# FNIRS_Carrier_BT_Series.net
KiCad netlist of a schematic drawn in EAGLE
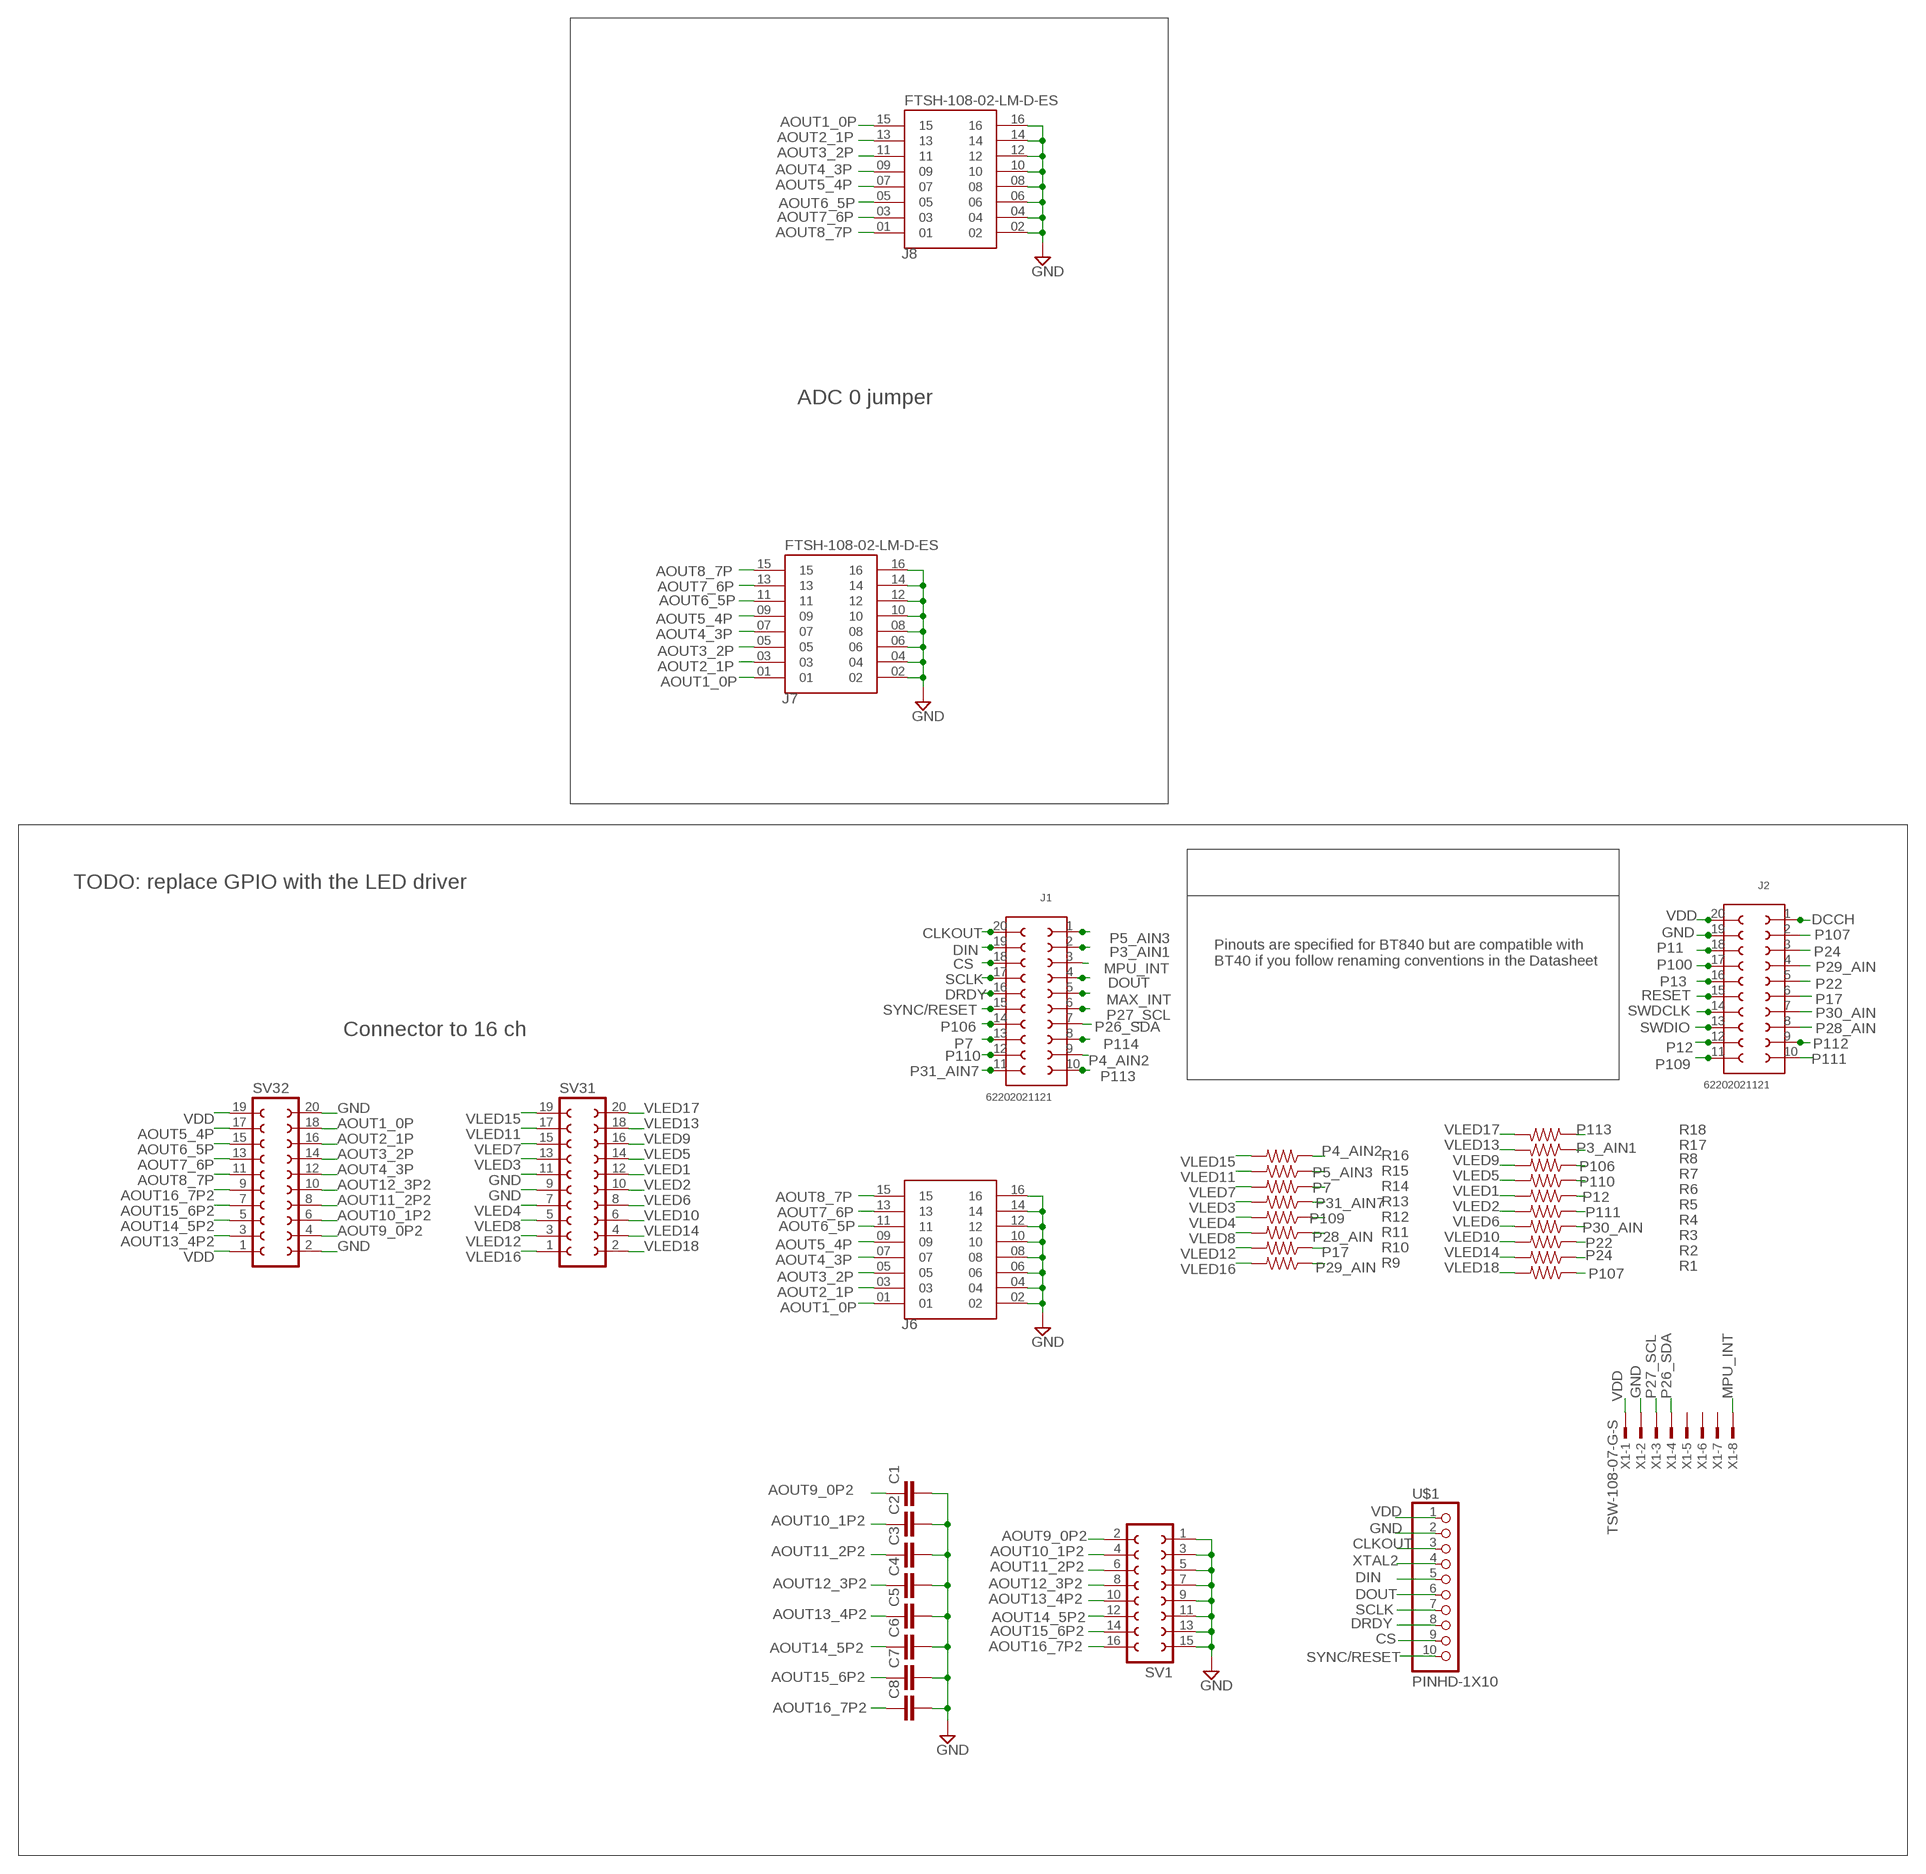
[diagram p0: schematic, sheet 1]

(export (version "E")
  (design (tool "Eeschema 10.0.6"))
  (components
    (comp (ref "C1")
      (value "C2.5/2")
      (footprint "eagle-import:C2.5-2")
      (libsource (lib "eagle-import") (part "C2.5/2"))
    )
    (comp (ref "C2")
      (value "C2.5/2")
      (footprint "eagle-import:C2.5-2")
      (libsource (lib "eagle-import") (part "C2.5/2"))
    )
    (comp (ref "C3")
      (value "C2.5/2")
      (footprint "eagle-import:C2.5-2")
      (libsource (lib "eagle-import") (part "C2.5/2"))
    )
    (comp (ref "C4")
      (value "C2.5/2")
      (footprint "eagle-import:C2.5-2")
      (libsource (lib "eagle-import") (part "C2.5/2"))
    )
    (comp (ref "C5")
      (value "C2.5/2")
      (footprint "eagle-import:C2.5-2")
      (libsource (lib "eagle-import") (part "C2.5/2"))
    )
    (comp (ref "C6")
      (value "C2.5/2")
      (footprint "eagle-import:C2.5-2")
      (libsource (lib "eagle-import") (part "C2.5/2"))
    )
    (comp (ref "C7")
      (value "C2.5/2")
      (footprint "eagle-import:C2.5-2")
      (libsource (lib "eagle-import") (part "C2.5/2"))
    )
    (comp (ref "C8")
      (value "C2.5/2")
      (footprint "eagle-import:C2.5-2")
      (libsource (lib "eagle-import") (part "C2.5/2"))
    )
    (comp (ref "J1")
      (value "62202021121")
      (footprint "eagle-import:62202021121")
      (fields (field (name "MF") "Würth Elektronik"))
      (libsource (lib "eagle-import") (part "62202021121"))
    )
    (comp (ref "J2")
      (value "62202021121")
      (footprint "eagle-import:62202021121")
      (fields (field (name "MF") "Würth Elektronik"))
      (libsource (lib "eagle-import") (part "62202021121"))
    )
    (comp (ref "J6")
      (value "FTSH-108-02-LM-D-ES")
      (footprint "eagle-import:SAMTEC_FTSH-108-02-LM-D-ES")
      (fields (field (name "MF") "Samtec"))
      (libsource (lib "eagle-import") (part "FTSH-108-02-LM-D-ES"))
    )
    (comp (ref "J7")
      (value "FTSH-108-02-LM-D-ES")
      (footprint "eagle-import:SAMTEC_FTSH-108-02-LM-D-ES")
      (fields (field (name "MF") "Samtec"))
      (libsource (lib "eagle-import") (part "FTSH-108-02-LM-D-ES"))
    )
    (comp (ref "J8")
      (value "FTSH-108-02-LM-D-ES")
      (footprint "eagle-import:SAMTEC_FTSH-108-02-LM-D-ES")
      (fields (field (name "MF") "Samtec"))
      (libsource (lib "eagle-import") (part "FTSH-108-02-LM-D-ES"))
    )
    (comp (ref "R1")
      (value "R-US_0204/5")
      (footprint "eagle-import:0204_5")
      (libsource (lib "eagle-import") (part "R-US_0204/5"))
    )
    (comp (ref "R2")
      (value "R-US_0204/5")
      (footprint "eagle-import:0204_5")
      (libsource (lib "eagle-import") (part "R-US_0204/5"))
    )
    (comp (ref "R3")
      (value "R-US_0204/5")
      (footprint "eagle-import:0204_5")
      (libsource (lib "eagle-import") (part "R-US_0204/5"))
    )
    (comp (ref "R4")
      (value "R-US_0204/5")
      (footprint "eagle-import:0204_5")
      (libsource (lib "eagle-import") (part "R-US_0204/5"))
    )
    (comp (ref "R5")
      (value "R-US_0204/5")
      (footprint "eagle-import:0204_5")
      (libsource (lib "eagle-import") (part "R-US_0204/5"))
    )
    (comp (ref "R6")
      (value "R-US_0204/5")
      (footprint "eagle-import:0204_5")
      (libsource (lib "eagle-import") (part "R-US_0204/5"))
    )
    (comp (ref "R7")
      (value "R-US_0204/5")
      (footprint "eagle-import:0204_5")
      (libsource (lib "eagle-import") (part "R-US_0204/5"))
    )
    (comp (ref "R8")
      (value "R-US_0204/5")
      (footprint "eagle-import:0204_5")
      (libsource (lib "eagle-import") (part "R-US_0204/5"))
    )
    (comp (ref "R9")
      (value "R-US_0204/5")
      (footprint "eagle-import:0204_5")
      (libsource (lib "eagle-import") (part "R-US_0204/5"))
    )
    (comp (ref "R10")
      (value "R-US_0204/5")
      (footprint "eagle-import:0204_5")
      (libsource (lib "eagle-import") (part "R-US_0204/5"))
    )
    (comp (ref "R11")
      (value "R-US_0204/5")
      (footprint "eagle-import:0204_5")
      (libsource (lib "eagle-import") (part "R-US_0204/5"))
    )
    (comp (ref "R12")
      (value "R-US_0204/5")
      (footprint "eagle-import:0204_5")
      (libsource (lib "eagle-import") (part "R-US_0204/5"))
    )
    (comp (ref "R13")
      (value "R-US_0204/5")
      (footprint "eagle-import:0204_5")
      (libsource (lib "eagle-import") (part "R-US_0204/5"))
    )
    (comp (ref "R14")
      (value "R-US_0204/5")
      (footprint "eagle-import:0204_5")
      (libsource (lib "eagle-import") (part "R-US_0204/5"))
    )
    (comp (ref "R15")
      (value "R-US_0204/5")
      (footprint "eagle-import:0204_5")
      (libsource (lib "eagle-import") (part "R-US_0204/5"))
    )
    (comp (ref "R16")
      (value "R-US_0204/5")
      (footprint "eagle-import:0204_5")
      (libsource (lib "eagle-import") (part "R-US_0204/5"))
    )
    (comp (ref "R17")
      (value "R-US_0204/5")
      (footprint "eagle-import:0204_5")
      (libsource (lib "eagle-import") (part "R-US_0204/5"))
    )
    (comp (ref "R18")
      (value "R-US_0204/5")
      (footprint "eagle-import:0204_5")
      (libsource (lib "eagle-import") (part "R-US_0204/5"))
    )
    (comp (ref "SV1")
      (value "FE08-2")
      (footprint "eagle-import:FE08-2")
      (libsource (lib "eagle-import") (part "FE08-2"))
    )
    (comp (ref "SV31")
      (value "FE10-2")
      (footprint "eagle-import:FE10-2")
      (libsource (lib "eagle-import") (part "FE10-2"))
    )
    (comp (ref "SV32")
      (value "FE10-2")
      (footprint "eagle-import:FE10-2")
      (libsource (lib "eagle-import") (part "FE10-2"))
    )
    (comp (ref "U$1")
      (value "PINHD-1X10")
      (footprint "eagle-import:1X10-BIG")
      (libsource (lib "eagle-import") (part "PINHD-1X10"))
    )
    (comp (ref "X1")
      (value "TSW-108-07-G-S")
      (footprint "eagle-import:TSW-108-XX-G-S")
      (fields (field (name "MF") "Samtec Inc."))
      (libsource (lib "eagle-import") (part "TSW-108--G-S07"))
    )
  )
  (nets
    (net (code "1") (name "AOUT1_0P") (class "Default")
      (node (ref "J6") (pin "01") (pinfunction "01_01") (pintype "passive"))
      (node (ref "J7") (pin "01") (pinfunction "01_01") (pintype "passive"))
      (node (ref "J8") (pin "15") (pinfunction "15_15") (pintype "passive"))
      (node (ref "SV32") (pin "18") (pinfunction "18_18") (pintype "passive"))
    )
    (net (code "2") (name "AOUT2_1P") (class "Default")
      (node (ref "J6") (pin "03") (pinfunction "03_03") (pintype "passive"))
      (node (ref "J7") (pin "03") (pinfunction "03_03") (pintype "passive"))
      (node (ref "J8") (pin "13") (pinfunction "13_13") (pintype "passive"))
      (node (ref "SV32") (pin "16") (pinfunction "16_16") (pintype "passive"))
    )
    (net (code "3") (name "AOUT3_2P") (class "Default")
      (node (ref "J6") (pin "05") (pinfunction "05_05") (pintype "passive"))
      (node (ref "J7") (pin "05") (pinfunction "05_05") (pintype "passive"))
      (node (ref "J8") (pin "11") (pinfunction "11_11") (pintype "passive"))
      (node (ref "SV32") (pin "14") (pinfunction "14_14") (pintype "passive"))
    )
    (net (code "4") (name "AOUT4_3P") (class "Default")
      (node (ref "J6") (pin "07") (pinfunction "07_07") (pintype "passive"))
      (node (ref "J7") (pin "07") (pinfunction "07_07") (pintype "passive"))
      (node (ref "J8") (pin "09") (pinfunction "09_09") (pintype "passive"))
      (node (ref "SV32") (pin "12") (pinfunction "12_12") (pintype "passive"))
    )
    (net (code "5") (name "AOUT5_4P") (class "Default")
      (node (ref "J6") (pin "09") (pinfunction "09_09") (pintype "passive"))
      (node (ref "J7") (pin "09") (pinfunction "09_09") (pintype "passive"))
      (node (ref "J8") (pin "07") (pinfunction "07_07") (pintype "passive"))
      (node (ref "SV32") (pin "17") (pinfunction "17_17") (pintype "passive"))
    )
    (net (code "6") (name "AOUT6_5P") (class "Default")
      (node (ref "J6") (pin "11") (pinfunction "11_11") (pintype "passive"))
      (node (ref "J7") (pin "11") (pinfunction "11_11") (pintype "passive"))
      (node (ref "J8") (pin "05") (pinfunction "05_05") (pintype "passive"))
      (node (ref "SV32") (pin "15") (pinfunction "15_15") (pintype "passive"))
    )
    (net (code "7") (name "AOUT7_6P") (class "Default")
      (node (ref "J6") (pin "13") (pinfunction "13_13") (pintype "passive"))
      (node (ref "J7") (pin "13") (pinfunction "13_13") (pintype "passive"))
      (node (ref "J8") (pin "03") (pinfunction "03_03") (pintype "passive"))
      (node (ref "SV32") (pin "13") (pinfunction "13_13") (pintype "passive"))
    )
    (net (code "8") (name "AOUT8_7P") (class "Default")
      (node (ref "J6") (pin "15") (pinfunction "15_15") (pintype "passive"))
      (node (ref "J7") (pin "15") (pinfunction "15_15") (pintype "passive"))
      (node (ref "J8") (pin "01") (pinfunction "01_01") (pintype "passive"))
      (node (ref "SV32") (pin "11") (pinfunction "11_11") (pintype "passive"))
    )
    (net (code "9") (name "AOUT9_0P2") (class "Default")
      (node (ref "C1") (pin "1") (pinfunction "1_1") (pintype "passive"))
      (node (ref "SV1") (pin "2") (pinfunction "2_2") (pintype "passive"))
      (node (ref "SV32") (pin "4") (pinfunction "4_4") (pintype "passive"))
    )
    (net (code "10") (name "AOUT10_1P2") (class "Default")
      (node (ref "C2") (pin "1") (pinfunction "1_1") (pintype "passive"))
      (node (ref "SV1") (pin "4") (pinfunction "4_4") (pintype "passive"))
      (node (ref "SV32") (pin "6") (pinfunction "6_6") (pintype "passive"))
    )
    (net (code "11") (name "AOUT11_2P2") (class "Default")
      (node (ref "C3") (pin "1") (pinfunction "1_1") (pintype "passive"))
      (node (ref "SV1") (pin "6") (pinfunction "6_6") (pintype "passive"))
      (node (ref "SV32") (pin "8") (pinfunction "8_8") (pintype "passive"))
    )
    (net (code "12") (name "AOUT12_3P2") (class "Default")
      (node (ref "C4") (pin "1") (pinfunction "1_1") (pintype "passive"))
      (node (ref "SV1") (pin "8") (pinfunction "8_8") (pintype "passive"))
      (node (ref "SV32") (pin "10") (pinfunction "10_10") (pintype "passive"))
    )
    (net (code "13") (name "AOUT13_4P2") (class "Default")
      (node (ref "C5") (pin "1") (pinfunction "1_1") (pintype "passive"))
      (node (ref "SV1") (pin "10") (pinfunction "10_10") (pintype "passive"))
      (node (ref "SV32") (pin "3") (pinfunction "3_3") (pintype "passive"))
    )
    (net (code "14") (name "AOUT14_5P2") (class "Default")
      (node (ref "C6") (pin "1") (pinfunction "1_1") (pintype "passive"))
      (node (ref "SV1") (pin "12") (pinfunction "12_12") (pintype "passive"))
      (node (ref "SV32") (pin "5") (pinfunction "5_5") (pintype "passive"))
    )
    (net (code "15") (name "AOUT15_6P2") (class "Default")
      (node (ref "C7") (pin "1") (pinfunction "1_1") (pintype "passive"))
      (node (ref "SV1") (pin "14") (pinfunction "14_14") (pintype "passive"))
      (node (ref "SV32") (pin "7") (pinfunction "7_7") (pintype "passive"))
    )
    (net (code "16") (name "AOUT16_7P2") (class "Default")
      (node (ref "C8") (pin "1") (pinfunction "1_1") (pintype "passive"))
      (node (ref "SV1") (pin "16") (pinfunction "16_16") (pintype "passive"))
      (node (ref "SV32") (pin "9") (pinfunction "9_9") (pintype "passive"))
    )
    (net (code "17") (name "CLKOUT") (class "Default")
      (node (ref "J1") (pin "20") (pinfunction "20_20") (pintype "passive"))
      (node (ref "U$1") (pin "3") (pinfunction "3_3") (pintype "passive"))
    )
    (net (code "18") (name "CS") (class "Default")
      (node (ref "J1") (pin "18") (pinfunction "18_18") (pintype "passive"))
      (node (ref "U$1") (pin "9") (pinfunction "9_9") (pintype "passive"))
    )
    (net (code "19") (name "DCCH") (class "Default")
      (node (ref "J2") (pin "1") (pinfunction "1_1") (pintype "passive"))
    )
    (net (code "20") (name "DIN") (class "Default")
      (node (ref "J1") (pin "19") (pinfunction "19_19") (pintype "passive"))
      (node (ref "U$1") (pin "5") (pinfunction "5_5") (pintype "passive"))
    )
    (net (code "21") (name "DOUT") (class "Default")
      (node (ref "J1") (pin "4") (pinfunction "4_4") (pintype "passive"))
      (node (ref "U$1") (pin "6") (pinfunction "6_6") (pintype "passive"))
    )
    (net (code "22") (name "DRDY") (class "Default")
      (node (ref "J1") (pin "16") (pinfunction "16_16") (pintype "passive"))
      (node (ref "U$1") (pin "8") (pinfunction "8_8") (pintype "passive"))
    )
    (net (code "23") (name "GND") (class "Default")
      (node (ref "C1") (pin "2") (pinfunction "2_2") (pintype "passive"))
      (node (ref "C2") (pin "2") (pinfunction "2_2") (pintype "passive"))
      (node (ref "C3") (pin "2") (pinfunction "2_2") (pintype "passive"))
      (node (ref "C4") (pin "2") (pinfunction "2_2") (pintype "passive"))
      (node (ref "C5") (pin "2") (pinfunction "2_2") (pintype "passive"))
      (node (ref "C6") (pin "2") (pinfunction "2_2") (pintype "passive"))
      (node (ref "C7") (pin "2") (pinfunction "2_2") (pintype "passive"))
      (node (ref "C8") (pin "2") (pinfunction "2_2") (pintype "passive"))
      (node (ref "J2") (pin "19") (pinfunction "19_19") (pintype "passive"))
      (node (ref "J6") (pin "02") (pinfunction "02_02") (pintype "passive"))
      (node (ref "J6") (pin "04") (pinfunction "04_04") (pintype "passive"))
      (node (ref "J6") (pin "06") (pinfunction "06_06") (pintype "passive"))
      (node (ref "J6") (pin "08") (pinfunction "08_08") (pintype "passive"))
      (node (ref "J6") (pin "10") (pinfunction "10_10") (pintype "passive"))
      (node (ref "J6") (pin "12") (pinfunction "12_12") (pintype "passive"))
      (node (ref "J6") (pin "14") (pinfunction "14_14") (pintype "passive"))
      (node (ref "J6") (pin "16") (pinfunction "16_16") (pintype "passive"))
      (node (ref "J7") (pin "02") (pinfunction "02_02") (pintype "passive"))
      (node (ref "J7") (pin "04") (pinfunction "04_04") (pintype "passive"))
      (node (ref "J7") (pin "06") (pinfunction "06_06") (pintype "passive"))
      (node (ref "J7") (pin "08") (pinfunction "08_08") (pintype "passive"))
      (node (ref "J7") (pin "10") (pinfunction "10_10") (pintype "passive"))
      (node (ref "J7") (pin "12") (pinfunction "12_12") (pintype "passive"))
      (node (ref "J7") (pin "14") (pinfunction "14_14") (pintype "passive"))
      (node (ref "J7") (pin "16") (pinfunction "16_16") (pintype "passive"))
      (node (ref "J8") (pin "02") (pinfunction "02_02") (pintype "passive"))
      (node (ref "J8") (pin "04") (pinfunction "04_04") (pintype "passive"))
      (node (ref "J8") (pin "06") (pinfunction "06_06") (pintype "passive"))
      (node (ref "J8") (pin "08") (pinfunction "08_08") (pintype "passive"))
      (node (ref "J8") (pin "10") (pinfunction "10_10") (pintype "passive"))
      (node (ref "J8") (pin "12") (pinfunction "12_12") (pintype "passive"))
      (node (ref "J8") (pin "14") (pinfunction "14_14") (pintype "passive"))
      (node (ref "J8") (pin "16") (pinfunction "16_16") (pintype "passive"))
      (node (ref "SV1") (pin "1") (pinfunction "1_1") (pintype "passive"))
      (node (ref "SV1") (pin "11") (pinfunction "11_11") (pintype "passive"))
      (node (ref "SV1") (pin "13") (pinfunction "13_13") (pintype "passive"))
      (node (ref "SV1") (pin "15") (pinfunction "15_15") (pintype "passive"))
      (node (ref "SV1") (pin "3") (pinfunction "3_3") (pintype "passive"))
      (node (ref "SV1") (pin "5") (pinfunction "5_5") (pintype "passive"))
      (node (ref "SV1") (pin "7") (pinfunction "7_7") (pintype "passive"))
      (node (ref "SV1") (pin "9") (pinfunction "9_9") (pintype "passive"))
      (node (ref "SV31") (pin "11") (pinfunction "11_11") (pintype "passive"))
      (node (ref "SV31") (pin "9") (pinfunction "9_9") (pintype "passive"))
      (node (ref "SV32") (pin "2") (pinfunction "2_2") (pintype "passive"))
      (node (ref "SV32") (pin "20") (pinfunction "20_20") (pintype "passive"))
      (node (ref "U$1") (pin "2") (pinfunction "2_2") (pintype "passive"))
      (node (ref "X1") (pin "2") (pinfunction "1_2") (pintype "passive"))
    )
    (net (code "24") (name "MAX_INT") (class "Default")
      (node (ref "J1") (pin "5") (pinfunction "5_5") (pintype "passive"))
    )
    (net (code "25") (name "MPU_INT") (class "Default")
      (node (ref "J1") (pin "3") (pinfunction "3_3") (pintype "passive"))
      (node (ref "X1") (pin "8") (pinfunction "1_8") (pintype "passive"))
    )
    (net (code "26") (name "P3_AIN1") (class "Default")
      (node (ref "J1") (pin "2") (pinfunction "2_2") (pintype "passive"))
      (node (ref "R17") (pin "1") (pinfunction "1_1") (pintype "passive"))
    )
    (net (code "27") (name "P4_AIN2") (class "Default")
      (node (ref "J1") (pin "9") (pinfunction "9_9") (pintype "passive"))
      (node (ref "R16") (pin "1") (pinfunction "1_1") (pintype "passive"))
    )
    (net (code "28") (name "P5_AIN3") (class "Default")
      (node (ref "J1") (pin "1") (pinfunction "1_1") (pintype "passive"))
      (node (ref "R15") (pin "1") (pinfunction "1_1") (pintype "passive"))
    )
    (net (code "29") (name "P7") (class "Default")
      (node (ref "J1") (pin "13") (pinfunction "13_13") (pintype "passive"))
      (node (ref "R14") (pin "1") (pinfunction "1_1") (pintype "passive"))
    )
    (net (code "30") (name "P11") (class "Default")
      (node (ref "J2") (pin "18") (pinfunction "18_18") (pintype "passive"))
    )
    (net (code "31") (name "P12") (class "Default")
      (node (ref "J2") (pin "12") (pinfunction "12_12") (pintype "passive"))
      (node (ref "R6") (pin "1") (pinfunction "1_1") (pintype "passive"))
    )
    (net (code "32") (name "P13") (class "Default")
      (node (ref "J2") (pin "16") (pinfunction "16_16") (pintype "passive"))
    )
    (net (code "33") (name "P17") (class "Default")
      (node (ref "J2") (pin "6") (pinfunction "6_6") (pintype "passive"))
      (node (ref "R10") (pin "1") (pinfunction "1_1") (pintype "passive"))
    )
    (net (code "34") (name "P22") (class "Default")
      (node (ref "J2") (pin "5") (pinfunction "5_5") (pintype "passive"))
      (node (ref "R3") (pin "1") (pinfunction "1_1") (pintype "passive"))
    )
    (net (code "35") (name "P24") (class "Default")
      (node (ref "J2") (pin "3") (pinfunction "3_3") (pintype "passive"))
      (node (ref "R2") (pin "1") (pinfunction "1_1") (pintype "passive"))
    )
    (net (code "36") (name "P26_SDA") (class "Default")
      (node (ref "J1") (pin "7") (pinfunction "7_7") (pintype "passive"))
      (node (ref "X1") (pin "4") (pinfunction "1_4") (pintype "passive"))
    )
    (net (code "37") (name "P27_SCL") (class "Default")
      (node (ref "J1") (pin "6") (pinfunction "6_6") (pintype "passive"))
      (node (ref "X1") (pin "3") (pinfunction "1_3") (pintype "passive"))
    )
    (net (code "38") (name "P28_AIN") (class "Default")
      (node (ref "J2") (pin "8") (pinfunction "8_8") (pintype "passive"))
      (node (ref "R11") (pin "1") (pinfunction "1_1") (pintype "passive"))
    )
    (net (code "39") (name "P29_AIN") (class "Default")
      (node (ref "J2") (pin "4") (pinfunction "4_4") (pintype "passive"))
      (node (ref "R9") (pin "1") (pinfunction "1_1") (pintype "passive"))
    )
    (net (code "40") (name "P30_AIN") (class "Default")
      (node (ref "J2") (pin "7") (pinfunction "7_7") (pintype "passive"))
      (node (ref "R4") (pin "1") (pinfunction "1_1") (pintype "passive"))
    )
    (net (code "41") (name "P31_AIN7") (class "Default")
      (node (ref "J1") (pin "11") (pinfunction "11_11") (pintype "passive"))
      (node (ref "R13") (pin "1") (pinfunction "1_1") (pintype "passive"))
    )
    (net (code "42") (name "P100") (class "Default")
      (node (ref "J2") (pin "17") (pinfunction "17_17") (pintype "passive"))
    )
    (net (code "43") (name "P106") (class "Default")
      (node (ref "J1") (pin "14") (pinfunction "14_14") (pintype "passive"))
      (node (ref "R8") (pin "1") (pinfunction "1_1") (pintype "passive"))
    )
    (net (code "44") (name "P107") (class "Default")
      (node (ref "J2") (pin "2") (pinfunction "2_2") (pintype "passive"))
      (node (ref "R1") (pin "1") (pinfunction "1_1") (pintype "passive"))
    )
    (net (code "45") (name "P109") (class "Default")
      (node (ref "J2") (pin "11") (pinfunction "11_11") (pintype "passive"))
      (node (ref "R12") (pin "1") (pinfunction "1_1") (pintype "passive"))
    )
    (net (code "46") (name "P110") (class "Default")
      (node (ref "J1") (pin "12") (pinfunction "12_12") (pintype "passive"))
      (node (ref "R7") (pin "1") (pinfunction "1_1") (pintype "passive"))
    )
    (net (code "47") (name "P111") (class "Default")
      (node (ref "J2") (pin "10") (pinfunction "10_10") (pintype "passive"))
      (node (ref "R5") (pin "1") (pinfunction "1_1") (pintype "passive"))
    )
    (net (code "48") (name "P112") (class "Default")
      (node (ref "J2") (pin "9") (pinfunction "9_9") (pintype "passive"))
    )
    (net (code "49") (name "P113") (class "Default")
      (node (ref "J1") (pin "10") (pinfunction "10_10") (pintype "passive"))
      (node (ref "R18") (pin "1") (pinfunction "1_1") (pintype "passive"))
    )
    (net (code "50") (name "P114") (class "Default")
      (node (ref "J1") (pin "8") (pinfunction "8_8") (pintype "passive"))
    )
    (net (code "51") (name "RESET") (class "Default")
      (node (ref "J2") (pin "15") (pinfunction "15_15") (pintype "passive"))
    )
    (net (code "52") (name "SCLK") (class "Default")
      (node (ref "J1") (pin "17") (pinfunction "17_17") (pintype "passive"))
      (node (ref "U$1") (pin "7") (pinfunction "7_7") (pintype "passive"))
    )
    (net (code "53") (name "SWDCLK") (class "Default")
      (node (ref "J2") (pin "14") (pinfunction "14_14") (pintype "passive"))
    )
    (net (code "54") (name "SWDIO") (class "Default")
      (node (ref "J2") (pin "13") (pinfunction "13_13") (pintype "passive"))
    )
    (net (code "55") (name "SYNC{slash}RESET") (class "Default")
      (node (ref "J1") (pin "15") (pinfunction "15_15") (pintype "passive"))
      (node (ref "U$1") (pin "10") (pinfunction "10_10") (pintype "passive"))
    )
    (net (code "56") (name "VDD") (class "Default")
      (node (ref "J2") (pin "20") (pinfunction "20_20") (pintype "passive"))
      (node (ref "SV32") (pin "1") (pinfunction "1_1") (pintype "passive"))
      (node (ref "SV32") (pin "19") (pinfunction "19_19") (pintype "passive"))
      (node (ref "U$1") (pin "1") (pinfunction "1_1") (pintype "passive"))
      (node (ref "X1") (pin "1") (pinfunction "1_1") (pintype "passive"))
    )
    (net (code "57") (name "VLED1") (class "Default")
      (node (ref "R6") (pin "2") (pinfunction "2_2") (pintype "passive"))
      (node (ref "SV31") (pin "12") (pinfunction "12_12") (pintype "passive"))
    )
    (net (code "58") (name "VLED2") (class "Default")
      (node (ref "R5") (pin "2") (pinfunction "2_2") (pintype "passive"))
      (node (ref "SV31") (pin "10") (pinfunction "10_10") (pintype "passive"))
    )
    (net (code "59") (name "VLED3") (class "Default")
      (node (ref "R13") (pin "2") (pinfunction "2_2") (pintype "passive"))
      (node (ref "SV31") (pin "13") (pinfunction "13_13") (pintype "passive"))
    )
    (net (code "60") (name "VLED4") (class "Default")
      (node (ref "R12") (pin "2") (pinfunction "2_2") (pintype "passive"))
      (node (ref "SV31") (pin "7") (pinfunction "7_7") (pintype "passive"))
    )
    (net (code "61") (name "VLED5") (class "Default")
      (node (ref "R7") (pin "2") (pinfunction "2_2") (pintype "passive"))
      (node (ref "SV31") (pin "14") (pinfunction "14_14") (pintype "passive"))
    )
    (net (code "62") (name "VLED6") (class "Default")
      (node (ref "R4") (pin "2") (pinfunction "2_2") (pintype "passive"))
      (node (ref "SV31") (pin "8") (pinfunction "8_8") (pintype "passive"))
    )
    (net (code "63") (name "VLED7") (class "Default")
      (node (ref "R14") (pin "2") (pinfunction "2_2") (pintype "passive"))
      (node (ref "SV31") (pin "15") (pinfunction "15_15") (pintype "passive"))
    )
    (net (code "64") (name "VLED8") (class "Default")
      (node (ref "R11") (pin "2") (pinfunction "2_2") (pintype "passive"))
      (node (ref "SV31") (pin "5") (pinfunction "5_5") (pintype "passive"))
    )
    (net (code "65") (name "VLED9") (class "Default")
      (node (ref "R8") (pin "2") (pinfunction "2_2") (pintype "passive"))
      (node (ref "SV31") (pin "16") (pinfunction "16_16") (pintype "passive"))
    )
    (net (code "66") (name "VLED10") (class "Default")
      (node (ref "R3") (pin "2") (pinfunction "2_2") (pintype "passive"))
      (node (ref "SV31") (pin "6") (pinfunction "6_6") (pintype "passive"))
    )
    (net (code "67") (name "VLED11") (class "Default")
      (node (ref "R15") (pin "2") (pinfunction "2_2") (pintype "passive"))
      (node (ref "SV31") (pin "17") (pinfunction "17_17") (pintype "passive"))
    )
    (net (code "68") (name "VLED12") (class "Default")
      (node (ref "R10") (pin "2") (pinfunction "2_2") (pintype "passive"))
      (node (ref "SV31") (pin "3") (pinfunction "3_3") (pintype "passive"))
    )
    (net (code "69") (name "VLED13") (class "Default")
      (node (ref "R17") (pin "2") (pinfunction "2_2") (pintype "passive"))
      (node (ref "SV31") (pin "18") (pinfunction "18_18") (pintype "passive"))
    )
    (net (code "70") (name "VLED14") (class "Default")
      (node (ref "R2") (pin "2") (pinfunction "2_2") (pintype "passive"))
      (node (ref "SV31") (pin "4") (pinfunction "4_4") (pintype "passive"))
    )
    (net (code "71") (name "VLED15") (class "Default")
      (node (ref "R16") (pin "2") (pinfunction "2_2") (pintype "passive"))
      (node (ref "SV31") (pin "19") (pinfunction "19_19") (pintype "passive"))
    )
    (net (code "72") (name "VLED16") (class "Default")
      (node (ref "R9") (pin "2") (pinfunction "2_2") (pintype "passive"))
      (node (ref "SV31") (pin "1") (pinfunction "1_1") (pintype "passive"))
    )
    (net (code "73") (name "VLED17") (class "Default")
      (node (ref "R18") (pin "2") (pinfunction "2_2") (pintype "passive"))
      (node (ref "SV31") (pin "20") (pinfunction "20_20") (pintype "passive"))
    )
    (net (code "74") (name "VLED18") (class "Default")
      (node (ref "R1") (pin "2") (pinfunction "2_2") (pintype "passive"))
      (node (ref "SV31") (pin "2") (pinfunction "2_2") (pintype "passive"))
    )
    (net (code "75") (name "XTAL2") (class "Default")
      (node (ref "U$1") (pin "4") (pinfunction "4_4") (pintype "passive"))
    )
    (net (code "76") (name "unconnected-(X1E-1-Pad5)") (class "Default")
      (node (ref "X1") (pin "5") (pinfunction "1_5") (pintype "passive"))
    )
    (net (code "77") (name "unconnected-(X1F-1-Pad6)") (class "Default")
      (node (ref "X1") (pin "6") (pinfunction "1_6") (pintype "passive"))
    )
    (net (code "78") (name "unconnected-(X1G-1-Pad7)") (class "Default")
      (node (ref "X1") (pin "7") (pinfunction "1_7") (pintype "passive"))
    )
  )
)
